# Sheet3.net
KiCad netlist of a schematic drawn in Altium Designer
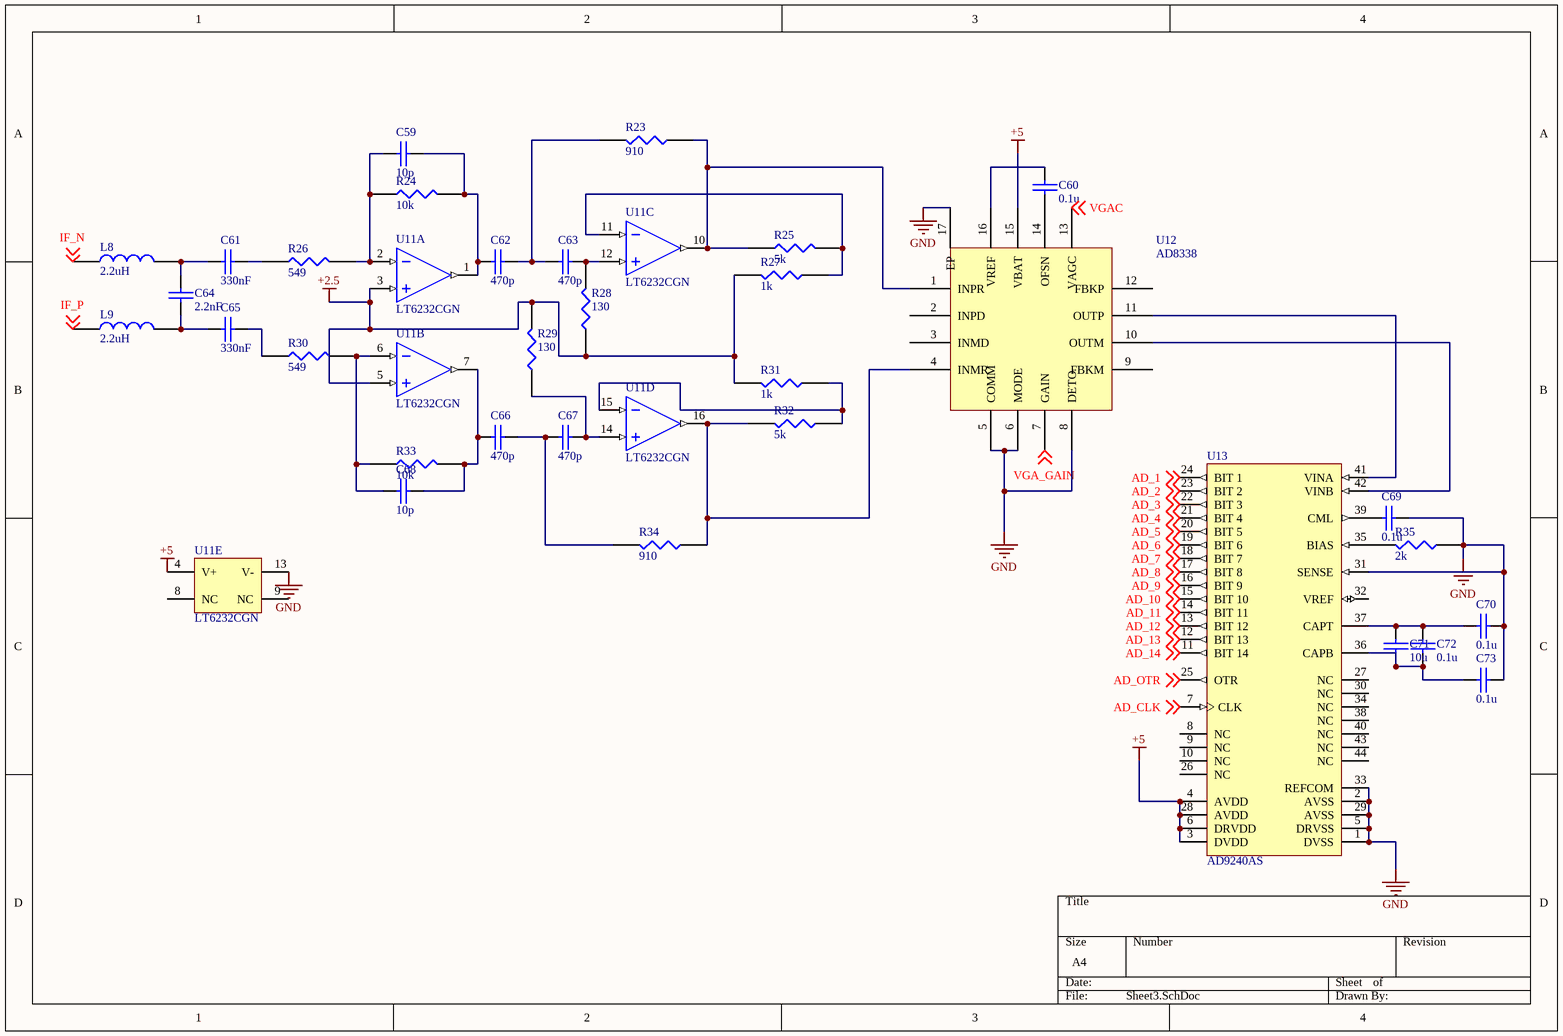
[diagram p0: Sheet3.SchDoc]

(export (version "E")
  (design (tool "Eeschema 10.0.6"))
  (components
    (comp (ref "C59")
      (value "10p")
      (footprint "0603_R")
      (description "Capacitor")
      (libsource (lib "Miscellaneous Devices") (part "CAP"))
    )
    (comp (ref "C60")
      (value "0.1u")
      (footprint "0603_R")
      (description "Capacitor")
      (libsource (lib "Miscellaneous Devices") (part "CAP"))
    )
    (comp (ref "C61")
      (value "330nF")
      (footprint "0603_R")
      (description "Capacitor")
      (libsource (lib "Miscellaneous Devices") (part "CAP"))
    )
    (comp (ref "C62")
      (value "470p")
      (footprint "0603_R")
      (description "Capacitor")
      (libsource (lib "Miscellaneous Devices") (part "CAP"))
    )
    (comp (ref "C63")
      (value "470p")
      (footprint "0603_R")
      (description "Capacitor")
      (libsource (lib "Miscellaneous Devices") (part "CAP"))
    )
    (comp (ref "C64")
      (value "2.2nF")
      (footprint "0603_R")
      (description "Capacitor")
      (libsource (lib "Miscellaneous Devices") (part "CAP"))
    )
    (comp (ref "C65")
      (value "330nF")
      (footprint "0603_R")
      (description "Capacitor")
      (libsource (lib "Miscellaneous Devices") (part "CAP"))
    )
    (comp (ref "C66")
      (value "470p")
      (footprint "0603_R")
      (description "Capacitor")
      (libsource (lib "Miscellaneous Devices") (part "CAP"))
    )
    (comp (ref "C67")
      (value "470p")
      (footprint "0603_R")
      (description "Capacitor")
      (libsource (lib "Miscellaneous Devices") (part "CAP"))
    )
    (comp (ref "C68")
      (value "10p")
      (footprint "0603_R")
      (description "Capacitor")
      (libsource (lib "Miscellaneous Devices") (part "CAP"))
    )
    (comp (ref "C69")
      (value "0.1u")
      (footprint "0603_R")
      (description "Capacitor")
      (libsource (lib "Miscellaneous Devices") (part "CAP"))
    )
    (comp (ref "C70")
      (value "0.1u")
      (footprint "0603_R")
      (description "Capacitor")
      (libsource (lib "Miscellaneous Devices") (part "CAP"))
    )
    (comp (ref "C71")
      (value "10u")
      (footprint "0603_R")
      (description "Capacitor")
      (libsource (lib "Miscellaneous Devices") (part "CAP"))
    )
    (comp (ref "C72")
      (value "0.1u")
      (footprint "0603_R")
      (description "Capacitor")
      (libsource (lib "Miscellaneous Devices") (part "CAP"))
    )
    (comp (ref "C73")
      (value "0.1u")
      (footprint "0603_R")
      (description "Capacitor")
      (libsource (lib "Miscellaneous Devices") (part "CAP"))
    )
    (comp (ref "L8")
      (value "2.2uH")
      (footprint "0603_R")
      (libsource (lib "Miscellaneous Devices") (part "INDUCTOR"))
    )
    (comp (ref "L9")
      (value "2.2uH")
      (footprint "0603_R")
      (libsource (lib "Miscellaneous Devices") (part "INDUCTOR"))
    )
    (comp (ref "R23")
      (value "910")
      (footprint "0603_R")
      (libsource (lib "Miscellaneous Devices") (part "RES1"))
    )
    (comp (ref "R24")
      (value "10k")
      (footprint "0603_R")
      (libsource (lib "Miscellaneous Devices") (part "RES1"))
    )
    (comp (ref "R25")
      (value "5k")
      (footprint "0603_R")
      (libsource (lib "Miscellaneous Devices") (part "RES1"))
    )
    (comp (ref "R26")
      (value "549")
      (footprint "0603_R")
      (libsource (lib "Miscellaneous Devices") (part "RES1"))
    )
    (comp (ref "R27")
      (value "1k")
      (footprint "0603_R")
      (libsource (lib "Miscellaneous Devices") (part "RES1"))
    )
    (comp (ref "R28")
      (value "130")
      (footprint "0603_R")
      (libsource (lib "Miscellaneous Devices") (part "RES1"))
    )
    (comp (ref "R29")
      (value "130")
      (footprint "0603_R")
      (libsource (lib "Miscellaneous Devices") (part "RES1"))
    )
    (comp (ref "R30")
      (value "549")
      (footprint "0603_R")
      (libsource (lib "Miscellaneous Devices") (part "RES1"))
    )
    (comp (ref "R31")
      (value "1k")
      (footprint "0603_R")
      (libsource (lib "Miscellaneous Devices") (part "RES1"))
    )
    (comp (ref "R32")
      (value "5k")
      (footprint "0603_R")
      (libsource (lib "Miscellaneous Devices") (part "RES1"))
    )
    (comp (ref "R33")
      (value "10k")
      (footprint "0603_R")
      (libsource (lib "Miscellaneous Devices") (part "RES1"))
    )
    (comp (ref "R34")
      (value "910")
      (footprint "0603_R")
      (libsource (lib "Miscellaneous Devices") (part "RES1"))
    )
    (comp (ref "R35")
      (value "2k")
      (footprint "0603_R")
      (libsource (lib "Miscellaneous Devices") (part "RES1"))
    )
    (comp (ref "U11")
      (value "LT6232CGN")
      (footprint "LT-GN-16_N")
      (fields
        (field (name "LINEAR TECHNOLOGY PART NUMBER") "LT6232")
        (field (name "MANUFACTURER") "Linear Technology")
      )
      (libsource (lib "Linear Technology Operational Amplifiers (LT2000-LT6000)") (part "LT6232CGN"))
    )
    (comp (ref "U12") (value "AD8338") (footprint "LCC16-AD8338") (libsource (lib "Proj") (part "AD8338")))
    (comp (ref "U13")
      (value "AD9240AS")
      (footprint "S-44-1_N")
      (fields (field (name "GENERIC PART NUMBER") "AD9240") (field (name "MANUFACTURER") "Analog Devices"))
      (libsource (lib "Analog Devices Data Converters Analog-to-Digital Converters") (part "AD9240AS"))
    )
  )
  (nets
    (net (code "1") (name "+2.5") (class "Default")
      (node (ref "R27") (pin "2") (pinfunction "2_2") (pintype "passive"))
      (node (ref "R28") (pin "1") (pinfunction "1_1") (pintype "passive"))
      (node (ref "R29") (pin "2") (pinfunction "2_2") (pintype "passive"))
      (node (ref "R31") (pin "2") (pinfunction "2_2") (pintype "passive"))
      (node (ref "U11") (pin "3") (pinfunction "+IN_A_3") (pintype "input"))
      (node (ref "U11") (pin "5") (pinfunction "+IN_B_5") (pintype "input"))
    )
    (net (code "2") (name "+5") (class "Default")
      (node (ref "U11") (pin "4") (pinfunction "V+_4") (pintype "power_in"))
      (node (ref "U12") (pin "15") (pinfunction "VBAT_15") (pintype "passive"))
      (node (ref "U13") (pin "28") (pinfunction "AVDD_28") (pintype "power_in"))
      (node (ref "U13") (pin "3") (pinfunction "DVDD_3") (pintype "power_in"))
      (node (ref "U13") (pin "4") (pinfunction "AVDD_4") (pintype "power_in"))
      (node (ref "U13") (pin "6") (pinfunction "DRVDD_6") (pintype "power_in"))
    )
    (net (code "3") (name "AD_1") (class "Default")
      (node (ref "U13") (pin "24") (pinfunction "BIT_1_24") (pintype "output"))
    )
    (net (code "4") (name "AD_2") (class "Default")
      (node (ref "U13") (pin "23") (pinfunction "BIT_2_23") (pintype "output"))
    )
    (net (code "5") (name "AD_3") (class "Default")
      (node (ref "U13") (pin "22") (pinfunction "BIT_3_22") (pintype "output"))
    )
    (net (code "6") (name "AD_4") (class "Default")
      (node (ref "U13") (pin "21") (pinfunction "BIT_4_21") (pintype "output"))
    )
    (net (code "7") (name "AD_5") (class "Default")
      (node (ref "U13") (pin "20") (pinfunction "BIT_5_20") (pintype "output"))
    )
    (net (code "8") (name "AD_6") (class "Default")
      (node (ref "U13") (pin "19") (pinfunction "BIT_6_19") (pintype "output"))
    )
    (net (code "9") (name "AD_7") (class "Default")
      (node (ref "U13") (pin "18") (pinfunction "BIT_7_18") (pintype "output"))
    )
    (net (code "10") (name "AD_8") (class "Default")
      (node (ref "U13") (pin "17") (pinfunction "BIT_8_17") (pintype "output"))
    )
    (net (code "11") (name "AD_9") (class "Default")
      (node (ref "U13") (pin "16") (pinfunction "BIT_9_16") (pintype "output"))
    )
    (net (code "12") (name "AD_10") (class "Default")
      (node (ref "U13") (pin "15") (pinfunction "BIT_10_15") (pintype "output"))
    )
    (net (code "13") (name "AD_11") (class "Default")
      (node (ref "U13") (pin "14") (pinfunction "BIT_11_14") (pintype "output"))
    )
    (net (code "14") (name "AD_12") (class "Default")
      (node (ref "U13") (pin "13") (pinfunction "BIT_12_13") (pintype "output"))
    )
    (net (code "15") (name "AD_13") (class "Default")
      (node (ref "U13") (pin "12") (pinfunction "BIT_13_12") (pintype "output"))
    )
    (net (code "16") (name "AD_14") (class "Default")
      (node (ref "U13") (pin "11") (pinfunction "BIT_14_11") (pintype "output"))
    )
    (net (code "17") (name "AD_CLK") (class "Default")
      (node (ref "U13") (pin "7") (pinfunction "CLK_7") (pintype "input"))
    )
    (net (code "18") (name "AD_OTR") (class "Default")
      (node (ref "U13") (pin "25") (pinfunction "OTR_25") (pintype "output"))
    )
    (net (code "19") (name "GND") (class "Default")
      (node (ref "C69") (pin "2") (pinfunction "2_2") (pintype "passive"))
      (node (ref "C70") (pin "2") (pinfunction "2_2") (pintype "passive"))
      (node (ref "C73") (pin "2") (pinfunction "2_2") (pintype "passive"))
      (node (ref "R35") (pin "1") (pinfunction "1_1") (pintype "passive"))
      (node (ref "U11") (pin "13") (pinfunction "V-_13") (pintype "power_in"))
      (node (ref "U12") (pin "17") (pinfunction "EP_17") (pintype "passive"))
      (node (ref "U12") (pin "5") (pinfunction "COMM_5") (pintype "passive"))
      (node (ref "U12") (pin "6") (pinfunction "MODE_6") (pintype "passive"))
      (node (ref "U12") (pin "8") (pinfunction "DETO_8") (pintype "passive"))
      (node (ref "U13") (pin "1") (pinfunction "DVSS_1") (pintype "power_in"))
      (node (ref "U13") (pin "2") (pinfunction "AVSS_2") (pintype "power_in"))
      (node (ref "U13") (pin "29") (pinfunction "AVSS_29") (pintype "power_in"))
      (node (ref "U13") (pin "31") (pinfunction "SENSE_31") (pintype "input"))
      (node (ref "U13") (pin "33") (pinfunction "REFCOM_33") (pintype "power_in"))
      (node (ref "U13") (pin "5") (pinfunction "DRVSS_5") (pintype "power_in"))
    )
    (net (code "20") (name "IF_N") (class "Default")
      (node (ref "L8") (pin "1") (pinfunction "1_1") (pintype "passive"))
    )
    (net (code "21") (name "IF_P") (class "Default")
      (node (ref "L9") (pin "1") (pinfunction "1_1") (pintype "passive"))
    )
    (net (code "22") (name "Net-(C61-Pad1)") (class "Default")
      (node (ref "C61") (pin "1") (pinfunction "1_1") (pintype "passive"))
      (node (ref "R26") (pin "1") (pinfunction "1_1") (pintype "passive"))
    )
    (net (code "23") (name "Net-(C61-Pad2)") (class "Default")
      (node (ref "C61") (pin "2") (pinfunction "2_2") (pintype "passive"))
      (node (ref "C64") (pin "2") (pinfunction "2_2") (pintype "passive"))
      (node (ref "L8") (pin "2") (pinfunction "2_2") (pintype "passive"))
    )
    (net (code "24") (name "Net-(C62-Pad1)") (class "Default")
      (node (ref "C62") (pin "1") (pinfunction "1_1") (pintype "passive"))
      (node (ref "C63") (pin "2") (pinfunction "2_2") (pintype "passive"))
      (node (ref "R23") (pin "2") (pinfunction "2_2") (pintype "passive"))
    )
    (net (code "25") (name "Net-(C64-Pad1)") (class "Default")
      (node (ref "C64") (pin "1") (pinfunction "1_1") (pintype "passive"))
      (node (ref "C65") (pin "2") (pinfunction "2_2") (pintype "passive"))
      (node (ref "L9") (pin "2") (pinfunction "2_2") (pintype "passive"))
    )
    (net (code "26") (name "Net-(C65-Pad1)") (class "Default")
      (node (ref "C65") (pin "1") (pinfunction "1_1") (pintype "passive"))
      (node (ref "R30") (pin "1") (pinfunction "1_1") (pintype "passive"))
    )
    (net (code "27") (name "Net-(C66-Pad1)") (class "Default")
      (node (ref "C66") (pin "1") (pinfunction "1_1") (pintype "passive"))
      (node (ref "C67") (pin "2") (pinfunction "2_2") (pintype "passive"))
      (node (ref "R34") (pin "2") (pinfunction "2_2") (pintype "passive"))
    )
    (net (code "28") (name "Net-(U11A--IN_A)") (class "Default")
      (node (ref "C59") (pin "2") (pinfunction "2_2") (pintype "passive"))
      (node (ref "R24") (pin "1") (pinfunction "1_1") (pintype "passive"))
      (node (ref "R26") (pin "2") (pinfunction "2_2") (pintype "passive"))
      (node (ref "U11") (pin "2") (pinfunction "-IN_A_2") (pintype "input"))
    )
    (net (code "29") (name "Net-(U11A-OUT_A)") (class "Default")
      (node (ref "C59") (pin "1") (pinfunction "1_1") (pintype "passive"))
      (node (ref "C62") (pin "2") (pinfunction "2_2") (pintype "passive"))
      (node (ref "R24") (pin "2") (pinfunction "2_2") (pintype "passive"))
      (node (ref "U11") (pin "1") (pinfunction "OUT_A_1") (pintype "output"))
    )
    (net (code "30") (name "Net-(U11B--IN_B)") (class "Default")
      (node (ref "C68") (pin "2") (pinfunction "2_2") (pintype "passive"))
      (node (ref "R30") (pin "2") (pinfunction "2_2") (pintype "passive"))
      (node (ref "R33") (pin "1") (pinfunction "1_1") (pintype "passive"))
      (node (ref "U11") (pin "6") (pinfunction "-IN_B_6") (pintype "input"))
    )
    (net (code "31") (name "Net-(U11B-OUT_B)") (class "Default")
      (node (ref "C66") (pin "2") (pinfunction "2_2") (pintype "passive"))
      (node (ref "C68") (pin "1") (pinfunction "1_1") (pintype "passive"))
      (node (ref "R33") (pin "2") (pinfunction "2_2") (pintype "passive"))
      (node (ref "U11") (pin "7") (pinfunction "OUT_B_7") (pintype "output"))
    )
    (net (code "32") (name "Net-(U11C-+IN_C)") (class "Default")
      (node (ref "C63") (pin "1") (pinfunction "1_1") (pintype "passive"))
      (node (ref "R28") (pin "2") (pinfunction "2_2") (pintype "passive"))
      (node (ref "U11") (pin "12") (pinfunction "+IN_C_12") (pintype "input"))
    )
    (net (code "33") (name "Net-(U11C--IN_C)") (class "Default")
      (node (ref "R25") (pin "2") (pinfunction "2_2") (pintype "passive"))
      (node (ref "R27") (pin "1") (pinfunction "1_1") (pintype "passive"))
      (node (ref "U11") (pin "11") (pinfunction "-IN_C_11") (pintype "input"))
    )
    (net (code "34") (name "Net-(U11C-OUT_C)") (class "Default")
      (node (ref "R23") (pin "1") (pinfunction "1_1") (pintype "passive"))
      (node (ref "R25") (pin "1") (pinfunction "1_1") (pintype "passive"))
      (node (ref "U11") (pin "10") (pinfunction "OUT_C_10") (pintype "output"))
      (node (ref "U12") (pin "1") (pinfunction "INPR_1") (pintype "passive"))
    )
    (net (code "35") (name "Net-(U11D-+IN_D)") (class "Default")
      (node (ref "C67") (pin "1") (pinfunction "1_1") (pintype "passive"))
      (node (ref "R29") (pin "1") (pinfunction "1_1") (pintype "passive"))
      (node (ref "U11") (pin "14") (pinfunction "+IN_D_14") (pintype "input"))
    )
    (net (code "36") (name "Net-(U11D--IN_D)") (class "Default")
      (node (ref "R31") (pin "1") (pinfunction "1_1") (pintype "passive"))
      (node (ref "R32") (pin "1") (pinfunction "1_1") (pintype "passive"))
      (node (ref "U11") (pin "15") (pinfunction "-IN_D_15") (pintype "input"))
    )
    (net (code "37") (name "Net-(U11D-OUT_D)") (class "Default")
      (node (ref "R32") (pin "2") (pinfunction "2_2") (pintype "passive"))
      (node (ref "R34") (pin "1") (pinfunction "1_1") (pintype "passive"))
      (node (ref "U11") (pin "16") (pinfunction "OUT_D_16") (pintype "output"))
      (node (ref "U12") (pin "4") (pinfunction "INMR_4") (pintype "passive"))
    )
    (net (code "38") (name "Net-(U12-OFSN)") (class "Default")
      (node (ref "C60") (pin "2") (pinfunction "2_2") (pintype "passive"))
      (node (ref "U12") (pin "14") (pinfunction "OFSN_14") (pintype "passive"))
    )
    (net (code "39") (name "Net-(U12-OUTM)") (class "Default")
      (node (ref "U12") (pin "10") (pinfunction "OUTM_10") (pintype "passive"))
      (node (ref "U13") (pin "42") (pinfunction "VINB_42") (pintype "input"))
    )
    (net (code "40") (name "Net-(U12-OUTP)") (class "Default")
      (node (ref "U12") (pin "11") (pinfunction "OUTP_11") (pintype "passive"))
      (node (ref "U13") (pin "41") (pinfunction "VINA_41") (pintype "input"))
    )
    (net (code "41") (name "Net-(U12-VREF)") (class "Default")
      (node (ref "C60") (pin "1") (pinfunction "1_1") (pintype "passive"))
      (node (ref "U12") (pin "16") (pinfunction "VREF_16") (pintype "passive"))
    )
    (net (code "42") (name "Net-(U13-BIAS)") (class "Default")
      (node (ref "R35") (pin "2") (pinfunction "2_2") (pintype "passive"))
      (node (ref "U13") (pin "35") (pinfunction "BIAS_35") (pintype "input"))
    )
    (net (code "43") (name "Net-(U13-CAPB)") (class "Default")
      (node (ref "C71") (pin "1") (pinfunction "1_1") (pintype "passive"))
      (node (ref "C72") (pin "1") (pinfunction "1_1") (pintype "passive"))
      (node (ref "C73") (pin "1") (pinfunction "1_1") (pintype "passive"))
      (node (ref "U13") (pin "36") (pinfunction "CAPB_36") (pintype "passive"))
    )
    (net (code "44") (name "Net-(U13-CAPT)") (class "Default")
      (node (ref "C70") (pin "1") (pinfunction "1_1") (pintype "passive"))
      (node (ref "C71") (pin "2") (pinfunction "2_2") (pintype "passive"))
      (node (ref "C72") (pin "2") (pinfunction "2_2") (pintype "passive"))
      (node (ref "U13") (pin "37") (pinfunction "CAPT_37") (pintype "passive"))
    )
    (net (code "45") (name "Net-(U13-CML)") (class "Default")
      (node (ref "C69") (pin "1") (pinfunction "1_1") (pintype "passive"))
      (node (ref "U13") (pin "39") (pinfunction "CML_39") (pintype "output"))
    )
    (net (code "46") (name "VGAC") (class "Default")
      (node (ref "U12") (pin "13") (pinfunction "VAGC_13") (pintype "passive"))
    )
    (net (code "47") (name "VGA_GAIN") (class "Default")
      (node (ref "U12") (pin "7") (pinfunction "GAIN_7") (pintype "passive"))
    )
    (net (code "48") (name "unconnected-(U11E-NC-Pad8)") (class "Default")
      (node (ref "U11") (pin "8") (pinfunction "NC_8") (pintype "passive"))
    )
    (net (code "49") (name "unconnected-(U11E-NC-Pad9)") (class "Default")
      (node (ref "U11") (pin "9") (pinfunction "NC_9") (pintype "passive"))
    )
    (net (code "50") (name "unconnected-(U12-FBKM-Pad9)") (class "Default")
      (node (ref "U12") (pin "9") (pinfunction "FBKM_9") (pintype "passive"))
    )
    (net (code "51") (name "unconnected-(U12-FBKP-Pad12)") (class "Default")
      (node (ref "U12") (pin "12") (pinfunction "FBKP_12") (pintype "passive"))
    )
    (net (code "52") (name "unconnected-(U12-INMD-Pad3)") (class "Default")
      (node (ref "U12") (pin "3") (pinfunction "INMD_3") (pintype "passive"))
    )
    (net (code "53") (name "unconnected-(U12-INPD-Pad2)") (class "Default")
      (node (ref "U12") (pin "2") (pinfunction "INPD_2") (pintype "passive"))
    )
    (net (code "54") (name "unconnected-(U13-NC-Pad8)") (class "Default")
      (node (ref "U13") (pin "8") (pinfunction "NC_8") (pintype "passive"))
    )
    (net (code "55") (name "unconnected-(U13-NC-Pad9)") (class "Default")
      (node (ref "U13") (pin "9") (pinfunction "NC_9") (pintype "passive"))
    )
    (net (code "56") (name "unconnected-(U13-NC-Pad10)") (class "Default")
      (node (ref "U13") (pin "10") (pinfunction "NC_10") (pintype "passive"))
    )
    (net (code "57") (name "unconnected-(U13-NC-Pad26)") (class "Default")
      (node (ref "U13") (pin "26") (pinfunction "NC_26") (pintype "passive"))
    )
    (net (code "58") (name "unconnected-(U13-NC-Pad27)") (class "Default")
      (node (ref "U13") (pin "27") (pinfunction "NC_27") (pintype "passive"))
    )
    (net (code "59") (name "unconnected-(U13-NC-Pad30)") (class "Default")
      (node (ref "U13") (pin "30") (pinfunction "NC_30") (pintype "passive"))
    )
    (net (code "60") (name "unconnected-(U13-NC-Pad34)") (class "Default")
      (node (ref "U13") (pin "34") (pinfunction "NC_34") (pintype "passive"))
    )
    (net (code "61") (name "unconnected-(U13-NC-Pad38)") (class "Default")
      (node (ref "U13") (pin "38") (pinfunction "NC_38") (pintype "passive"))
    )
    (net (code "62") (name "unconnected-(U13-NC-Pad40)") (class "Default")
      (node (ref "U13") (pin "40") (pinfunction "NC_40") (pintype "passive"))
    )
    (net (code "63") (name "unconnected-(U13-NC-Pad43)") (class "Default")
      (node (ref "U13") (pin "43") (pinfunction "NC_43") (pintype "passive"))
    )
    (net (code "64") (name "unconnected-(U13-NC-Pad44)") (class "Default")
      (node (ref "U13") (pin "44") (pinfunction "NC_44") (pintype "passive"))
    )
    (net (code "65") (name "unconnected-(U13-VREF-Pad32)") (class "Default")
      (node (ref "U13") (pin "32") (pinfunction "VREF_32") (pintype "bidirectional"))
    )
  )
)
